# CATS-GS-PM.net
KiCad netlist of a schematic drawn in Altium Designer
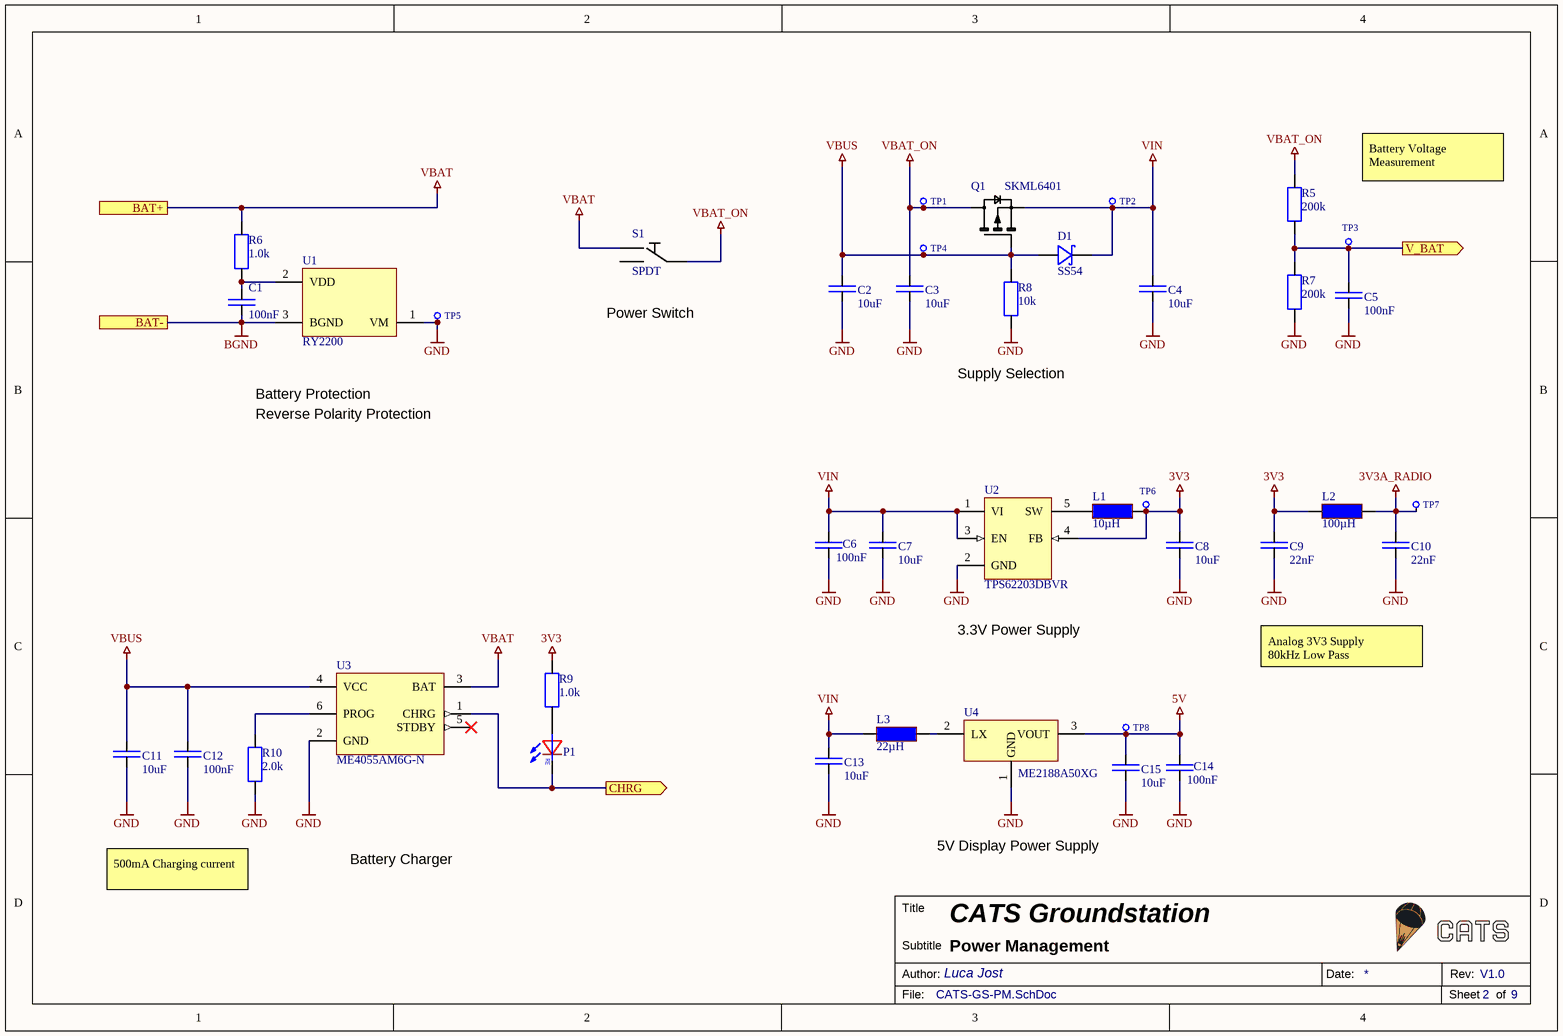
[diagram p0: CATS-GS-PM.SchDoc]

(export (version "E")
  (design (tool "Eeschema 10.0.6"))
  (components
    (comp (ref "C1")
      (value "100nF")
      (footprint "SMD Keramikkondensator 0402")
      (description "SMD Ceramic Capacitor E6")
      (libsource (lib "Ceramic Capacitors-E6") (part "E6 - 100nF"))
    )
    (comp (ref "C2")
      (value "10uF")
      (footprint "SMD Keramikkondensator 0603")
      (description "SMD Ceramic Capacitor E6")
      (libsource (lib "Ceramic Capacitors-E6") (part "E6 - 10uF"))
    )
    (comp (ref "C3")
      (value "10uF")
      (footprint "SMD Keramikkondensator 0603")
      (description "SMD Ceramic Capacitor E6")
      (libsource (lib "Ceramic Capacitors-E6") (part "E6 - 10uF"))
    )
    (comp (ref "C4")
      (value "10uF")
      (footprint "SMD Keramikkondensator 0603")
      (description "SMD Ceramic Capacitor E6")
      (libsource (lib "Ceramic Capacitors-E6") (part "E6 - 10uF"))
    )
    (comp (ref "C5")
      (value "100nF")
      (footprint "SMD Keramikkondensator 0402")
      (description "SMD Ceramic Capacitor E6")
      (libsource (lib "Ceramic Capacitors-E6") (part "E6 - 100nF"))
    )
    (comp (ref "C6")
      (value "100nF")
      (footprint "SMD Keramikkondensator 0402")
      (description "SMD Ceramic Capacitor E6")
      (libsource (lib "Ceramic Capacitors-E6") (part "E6 - 100nF"))
    )
    (comp (ref "C7")
      (value "10uF")
      (footprint "SMD Keramikkondensator 0603")
      (description "SMD Ceramic Capacitor E6")
      (libsource (lib "Ceramic Capacitors-E6") (part "E6 - 10uF"))
    )
    (comp (ref "C8")
      (value "10uF")
      (footprint "SMD Keramikkondensator 0603")
      (description "SMD Ceramic Capacitor E6")
      (libsource (lib "Ceramic Capacitors-E6") (part "E6 - 10uF"))
    )
    (comp (ref "C9")
      (value "22nF")
      (footprint "SMD Keramikkondensator 0603")
      (description "SMD Ceramic Capacitor E6")
      (libsource (lib "Ceramic Capacitors-E6") (part "E6 - 22nF"))
    )
    (comp (ref "C10")
      (value "22nF")
      (footprint "SMD Keramikkondensator 0603")
      (description "SMD Ceramic Capacitor E6")
      (libsource (lib "Ceramic Capacitors-E6") (part "E6 - 22nF"))
    )
    (comp (ref "C11")
      (value "10uF")
      (footprint "SMD Keramikkondensator 0603")
      (description "SMD Ceramic Capacitor E6")
      (libsource (lib "Ceramic Capacitors-E6") (part "E6 - 10uF"))
    )
    (comp (ref "C12")
      (value "100nF")
      (footprint "SMD Keramikkondensator 0402")
      (description "SMD Ceramic Capacitor E6")
      (libsource (lib "Ceramic Capacitors-E6") (part "E6 - 100nF"))
    )
    (comp (ref "C13")
      (value "10uF")
      (footprint "SMD Keramikkondensator 0603")
      (description "SMD Ceramic Capacitor E6")
      (libsource (lib "Ceramic Capacitors-E6") (part "E6 - 10uF"))
    )
    (comp (ref "C14")
      (value "100nF")
      (footprint "SMD Keramikkondensator 0402")
      (description "SMD Ceramic Capacitor E6")
      (libsource (lib "Ceramic Capacitors-E6") (part "E6 - 100nF"))
    )
    (comp (ref "C15")
      (value "10uF")
      (footprint "SMD Keramikkondensator 0603")
      (description "SMD Ceramic Capacitor E6")
      (libsource (lib "Ceramic Capacitors-E6") (part "E6 - 10uF"))
    )
    (comp (ref "D1")
      (value "SS54")
      (footprint "SMD Diode DO-214-AC")
      (description "40V 5A 550mV @ 5A SMA(DO-214AC) Schottky Barrier Diodes (SBD) ROHS")
      (libsource (lib "Diodes") (part "SS54"))
    )
    (comp (ref "L1")
      (value "10µH")
      (footprint "SMD Inductor 4x4x1.8")
      (description "165mOhm SMD, 1.6A")
      (libsource (lib "Inductors") (part "Inductor 10µH / 1.6A"))
    )
    (comp (ref "L2")
      (value "100µH")
      (footprint "SMD Inductor 1812")
      (description "0.25A 100µH ±20% 144mΩ SMD Power Inductors")
      (libsource (lib "Inductors") (part "Inductor 100µH / 0.25A"))
    )
    (comp (ref "L3")
      (value "22µH")
      (footprint "SMD Inductor 4x4x1.8")
      (description "350mOhm SMD, 1A")
      (libsource (lib "Inductors") (part "Inductor 22µH / 1A"))
    )
    (comp (ref "P1")
      (value "LED")
      (footprint "SMD LED 0603")
      (description "Color LED")
      (libsource (lib "Diodes") (part "LED"))
    )
    (comp (ref "Q1")
      (value "SKML6401")
      (footprint "SMD MOSFET SOT-23")
      (description "P Channel MOSFET, 16V 3A, SOT-23")
      (libsource (lib "Electronic Switches") (part "SKML6401"))
    )
    (comp (ref "R5")
      (value "200k")
      (footprint "SMD Widerstand 0402")
      (description "SMD Chip Resistor E24")
      (libsource (lib "Resistors-E24") (part "E24 - 200k"))
    )
    (comp (ref "R6")
      (value "1.0k")
      (footprint "SMD Widerstand 0402")
      (description "SMD Chip Resistor E24")
      (libsource (lib "Resistors-E24") (part "E24 - 1.0k"))
    )
    (comp (ref "R7")
      (value "200k")
      (footprint "SMD Widerstand 0402")
      (description "SMD Chip Resistor E24")
      (libsource (lib "Resistors-E24") (part "E24 - 200k"))
    )
    (comp (ref "R8")
      (value "10k")
      (footprint "SMD Widerstand 0402")
      (description "SMD Chip Resistor E24")
      (libsource (lib "Resistors-E24") (part "E24 - 10k"))
    )
    (comp (ref "R9")
      (value "1.0k")
      (footprint "SMD Widerstand 0402")
      (description "SMD Chip Resistor E24")
      (libsource (lib "Resistors-E24") (part "E24 - 1.0k"))
    )
    (comp (ref "R10")
      (value "2.0k")
      (footprint "SMD Widerstand 0402")
      (description "SMD Chip Resistor E24")
      (libsource (lib "Resistors-E24") (part "E24 - 2.0k"))
    )
    (comp (ref "S1")
      (value "SPDT")
      (footprint "SMD Switch SPDT 90° G-Switch")
      (description "Slide Switch SPDT SMD")
      (libsource (lib "Switches") (part "Switch SPDT G-Switch"))
    )
    (comp (ref "TP1")
      (value "X-TP")
      (footprint "SMD Testpoint 1mm")
      (description "Testpunkt")
      (libsource (lib "VLD-Monitor_V1.0") (part "X-TP"))
    )
    (comp (ref "TP2")
      (value "X-TP")
      (footprint "SMD Testpoint 1mm")
      (description "Testpunkt")
      (libsource (lib "VLD-Monitor_V1.0") (part "X-TP"))
    )
    (comp (ref "TP3")
      (value "X-TP")
      (footprint "SMD Testpoint 1mm")
      (description "Testpunkt")
      (libsource (lib "Fleet-Monitor") (part "X-TP"))
    )
    (comp (ref "TP4")
      (value "X-TP")
      (footprint "SMD Testpoint 1mm")
      (description "Testpunkt")
      (libsource (lib "VLD-Monitor_V1.0") (part "X-TP"))
    )
    (comp (ref "TP5")
      (value "X-TP")
      (footprint "SMD Testpoint 1mm")
      (description "Testpunkt")
      (libsource (lib "VLD-Monitor_V1.0") (part "X-TP"))
    )
    (comp (ref "TP6")
      (value "X-TP")
      (footprint "SMD Testpoint 1mm")
      (description "Testpunkt")
      (libsource (lib "Fleet-Monitor") (part "X-TP"))
    )
    (comp (ref "TP7")
      (value "X-TP")
      (footprint "SMD Testpoint 1mm")
      (description "Testpunkt")
      (libsource (lib "VLD-Monitor_V1.0") (part "X-TP"))
    )
    (comp (ref "TP8")
      (value "X-TP")
      (footprint "SMD Testpoint 1mm")
      (description "Testpunkt")
      (libsource (lib "VLD-Monitor_V1.0") (part "X-TP"))
    )
    (comp (ref "U1")
      (value "RY2200")
      (footprint "SMD IC SOT-23")
      (description "One Cell Li-ion and Li-poly Battery Protection IC")
      (libsource (lib "Power Management") (part "RY2200"))
    )
    (comp (ref "U2")
      (value "TPS62203DBVR")
      (footprint "SMD IC SOT-23-5")
      (libsource (lib "Voltage-Converter") (part "TPS62203DBVR"))
    )
    (comp (ref "U3")
      (value "ME4055AM6G-N")
      (footprint "SMD IC SOT-23-6")
      (description "800mA Lithium Ion Battery Linear Charger")
      (libsource (lib "Voltage-Converter") (part "ME4055AM6G-N"))
    )
    (comp (ref "U4")
      (value "ME2188A50XG")
      (footprint "SMD IC SOT-23")
      (description "Fixed 5V Boost Converter")
      (libsource (lib "Voltage-Converter") (part "ME2188A50XG"))
    )
  )
  (nets
    (net (code "1") (name "/CHRG") (class "Default")
      (node (ref "P1") (pin "K") (pinfunction "K_K") (pintype "passive"))
      (node (ref "U3") (pin "1") (pinfunction "CHRG_1") (pintype "output"))
    )
    (net (code "2") (name "/V_BAT") (class "Default")
      (node (ref "C5") (pin "2") (pinfunction "2_2") (pintype "passive"))
      (node (ref "R5") (pin "1") (pinfunction "1_1") (pintype "passive"))
      (node (ref "R7") (pin "2") (pinfunction "2_2") (pintype "passive"))
      (node (ref "TP3") (pin "1") (pinfunction "1_1") (pintype "passive"))
    )
    (net (code "3") (name "3V3") (class "Default")
      (node (ref "C8") (pin "2") (pinfunction "2_2") (pintype "passive"))
      (node (ref "C9") (pin "2") (pinfunction "2_2") (pintype "passive"))
      (node (ref "L1") (pin "2") (pinfunction "2_2") (pintype "passive"))
      (node (ref "L2") (pin "1") (pinfunction "1_1") (pintype "passive"))
      (node (ref "R9") (pin "2") (pinfunction "2_2") (pintype "passive"))
      (node (ref "TP6") (pin "1") (pinfunction "1_1") (pintype "passive"))
      (node (ref "U2") (pin "4") (pinfunction "FB_4") (pintype "input"))
    )
    (net (code "4") (name "3V3A_RADIO") (class "Default")
      (node (ref "C10") (pin "2") (pinfunction "2_2") (pintype "passive"))
      (node (ref "L2") (pin "2") (pinfunction "2_2") (pintype "passive"))
      (node (ref "TP7") (pin "1") (pinfunction "1_1") (pintype "passive"))
    )
    (net (code "5") (name "5V") (class "Default")
      (node (ref "C14") (pin "2") (pinfunction "2_2") (pintype "passive"))
      (node (ref "C15") (pin "2") (pinfunction "2_2") (pintype "passive"))
      (node (ref "TP8") (pin "1") (pinfunction "1_1") (pintype "passive"))
      (node (ref "U4") (pin "3") (pinfunction "VOUT_3") (pintype "passive"))
    )
    (net (code "6") (name "BGND") (class "Default")
      (node (ref "C1") (pin "1") (pinfunction "1_1") (pintype "passive"))
      (node (ref "U1") (pin "3") (pinfunction "BGND_3") (pintype "passive"))
    )
    (net (code "7") (name "GND") (class "Default")
      (node (ref "C10") (pin "1") (pinfunction "1_1") (pintype "passive"))
      (node (ref "C11") (pin "1") (pinfunction "1_1") (pintype "passive"))
      (node (ref "C12") (pin "1") (pinfunction "1_1") (pintype "passive"))
      (node (ref "C13") (pin "1") (pinfunction "1_1") (pintype "passive"))
      (node (ref "C14") (pin "1") (pinfunction "1_1") (pintype "passive"))
      (node (ref "C15") (pin "1") (pinfunction "1_1") (pintype "passive"))
      (node (ref "C2") (pin "1") (pinfunction "1_1") (pintype "passive"))
      (node (ref "C3") (pin "1") (pinfunction "1_1") (pintype "passive"))
      (node (ref "C4") (pin "1") (pinfunction "1_1") (pintype "passive"))
      (node (ref "C5") (pin "1") (pinfunction "1_1") (pintype "passive"))
      (node (ref "C6") (pin "1") (pinfunction "1_1") (pintype "passive"))
      (node (ref "C7") (pin "1") (pinfunction "1_1") (pintype "passive"))
      (node (ref "C8") (pin "1") (pinfunction "1_1") (pintype "passive"))
      (node (ref "C9") (pin "1") (pinfunction "1_1") (pintype "passive"))
      (node (ref "R10") (pin "1") (pinfunction "1_1") (pintype "passive"))
      (node (ref "R7") (pin "1") (pinfunction "1_1") (pintype "passive"))
      (node (ref "R8") (pin "1") (pinfunction "1_1") (pintype "passive"))
      (node (ref "TP5") (pin "1") (pinfunction "1_1") (pintype "passive"))
      (node (ref "U1") (pin "1") (pinfunction "VM_1") (pintype "passive"))
      (node (ref "U2") (pin "2") (pinfunction "GND_2") (pintype "passive"))
      (node (ref "U3") (pin "2") (pinfunction "GND_2") (pintype "passive"))
      (node (ref "U4") (pin "1") (pinfunction "GND_1") (pintype "passive"))
    )
    (net (code "8") (name "Net-(P1-PadA)") (class "Default")
      (node (ref "P1") (pin "A") (pinfunction "A_A") (pintype "passive"))
      (node (ref "R9") (pin "1") (pinfunction "1_1") (pintype "passive"))
    )
    (net (code "9") (name "Net-(U1-VDD)") (class "Default")
      (node (ref "C1") (pin "2") (pinfunction "2_2") (pintype "passive"))
      (node (ref "R6") (pin "1") (pinfunction "1_1") (pintype "passive"))
      (node (ref "U1") (pin "2") (pinfunction "VDD_2") (pintype "passive"))
    )
    (net (code "10") (name "Net-(U2-SW)") (class "Default")
      (node (ref "L1") (pin "1") (pinfunction "1_1") (pintype "passive"))
      (node (ref "U2") (pin "5") (pinfunction "SW_5") (pintype "passive"))
    )
    (net (code "11") (name "Net-(U3-PROG)") (class "Default")
      (node (ref "R10") (pin "2") (pinfunction "2_2") (pintype "passive"))
      (node (ref "U3") (pin "6") (pinfunction "PROG_6") (pintype "passive"))
    )
    (net (code "12") (name "Net-(U4-LX)") (class "Default")
      (node (ref "L3") (pin "2") (pinfunction "2_2") (pintype "passive"))
      (node (ref "U4") (pin "2") (pinfunction "LX_2") (pintype "passive"))
    )
    (net (code "13") (name "VBAT") (class "Default")
      (node (ref "R6") (pin "2") (pinfunction "2_2") (pintype "passive"))
      (node (ref "S1") (pin "3") (pintype "passive"))
      (node (ref "U3") (pin "3") (pinfunction "BAT_3") (pintype "passive"))
    )
    (net (code "14") (name "VBAT_ON") (class "Default")
      (node (ref "C3") (pin "2") (pinfunction "2_2") (pintype "passive"))
      (node (ref "Q1") (pin "D") (pinfunction "D_D") (pintype "passive"))
      (node (ref "R5") (pin "2") (pinfunction "2_2") (pintype "passive"))
      (node (ref "S1") (pin "2") (pintype "passive"))
      (node (ref "TP1") (pin "1") (pinfunction "1_1") (pintype "passive"))
    )
    (net (code "15") (name "VBUS") (class "Default")
      (node (ref "C11") (pin "2") (pinfunction "2_2") (pintype "passive"))
      (node (ref "C12") (pin "2") (pinfunction "2_2") (pintype "passive"))
      (node (ref "C2") (pin "2") (pinfunction "2_2") (pintype "passive"))
      (node (ref "D1") (pin "A") (pinfunction "A_A") (pintype "passive"))
      (node (ref "Q1") (pin "G") (pinfunction "G_G") (pintype "passive"))
      (node (ref "R8") (pin "2") (pinfunction "2_2") (pintype "passive"))
      (node (ref "TP4") (pin "1") (pinfunction "1_1") (pintype "passive"))
      (node (ref "U3") (pin "4") (pinfunction "VCC_4") (pintype "passive"))
    )
    (net (code "16") (name "VIN") (class "Default")
      (node (ref "C13") (pin "2") (pinfunction "2_2") (pintype "passive"))
      (node (ref "C4") (pin "2") (pinfunction "2_2") (pintype "passive"))
      (node (ref "C6") (pin "2") (pinfunction "2_2") (pintype "passive"))
      (node (ref "C7") (pin "2") (pinfunction "2_2") (pintype "passive"))
      (node (ref "D1") (pin "K") (pinfunction "K_K") (pintype "passive"))
      (node (ref "L3") (pin "1") (pinfunction "1_1") (pintype "passive"))
      (node (ref "Q1") (pin "S") (pinfunction "S_S") (pintype "passive"))
      (node (ref "TP2") (pin "1") (pinfunction "1_1") (pintype "passive"))
      (node (ref "U2") (pin "1") (pinfunction "VI_1") (pintype "passive"))
      (node (ref "U2") (pin "3") (pinfunction "EN_3") (pintype "input"))
    )
    (net (code "17") (name "unconnected-(S1-Pad1)") (class "Default")
      (node (ref "S1") (pin "1") (pintype "passive"))
    )
    (net (code "18") (name "unconnected-(U3-STDBY-Pad5)") (class "Default")
      (node (ref "U3") (pin "5") (pinfunction "STDBY_5") (pintype "output+no_connect"))
    )
  )
)
